# genPWM.net
KiCad netlist of a schematic drawn in Altium Designer
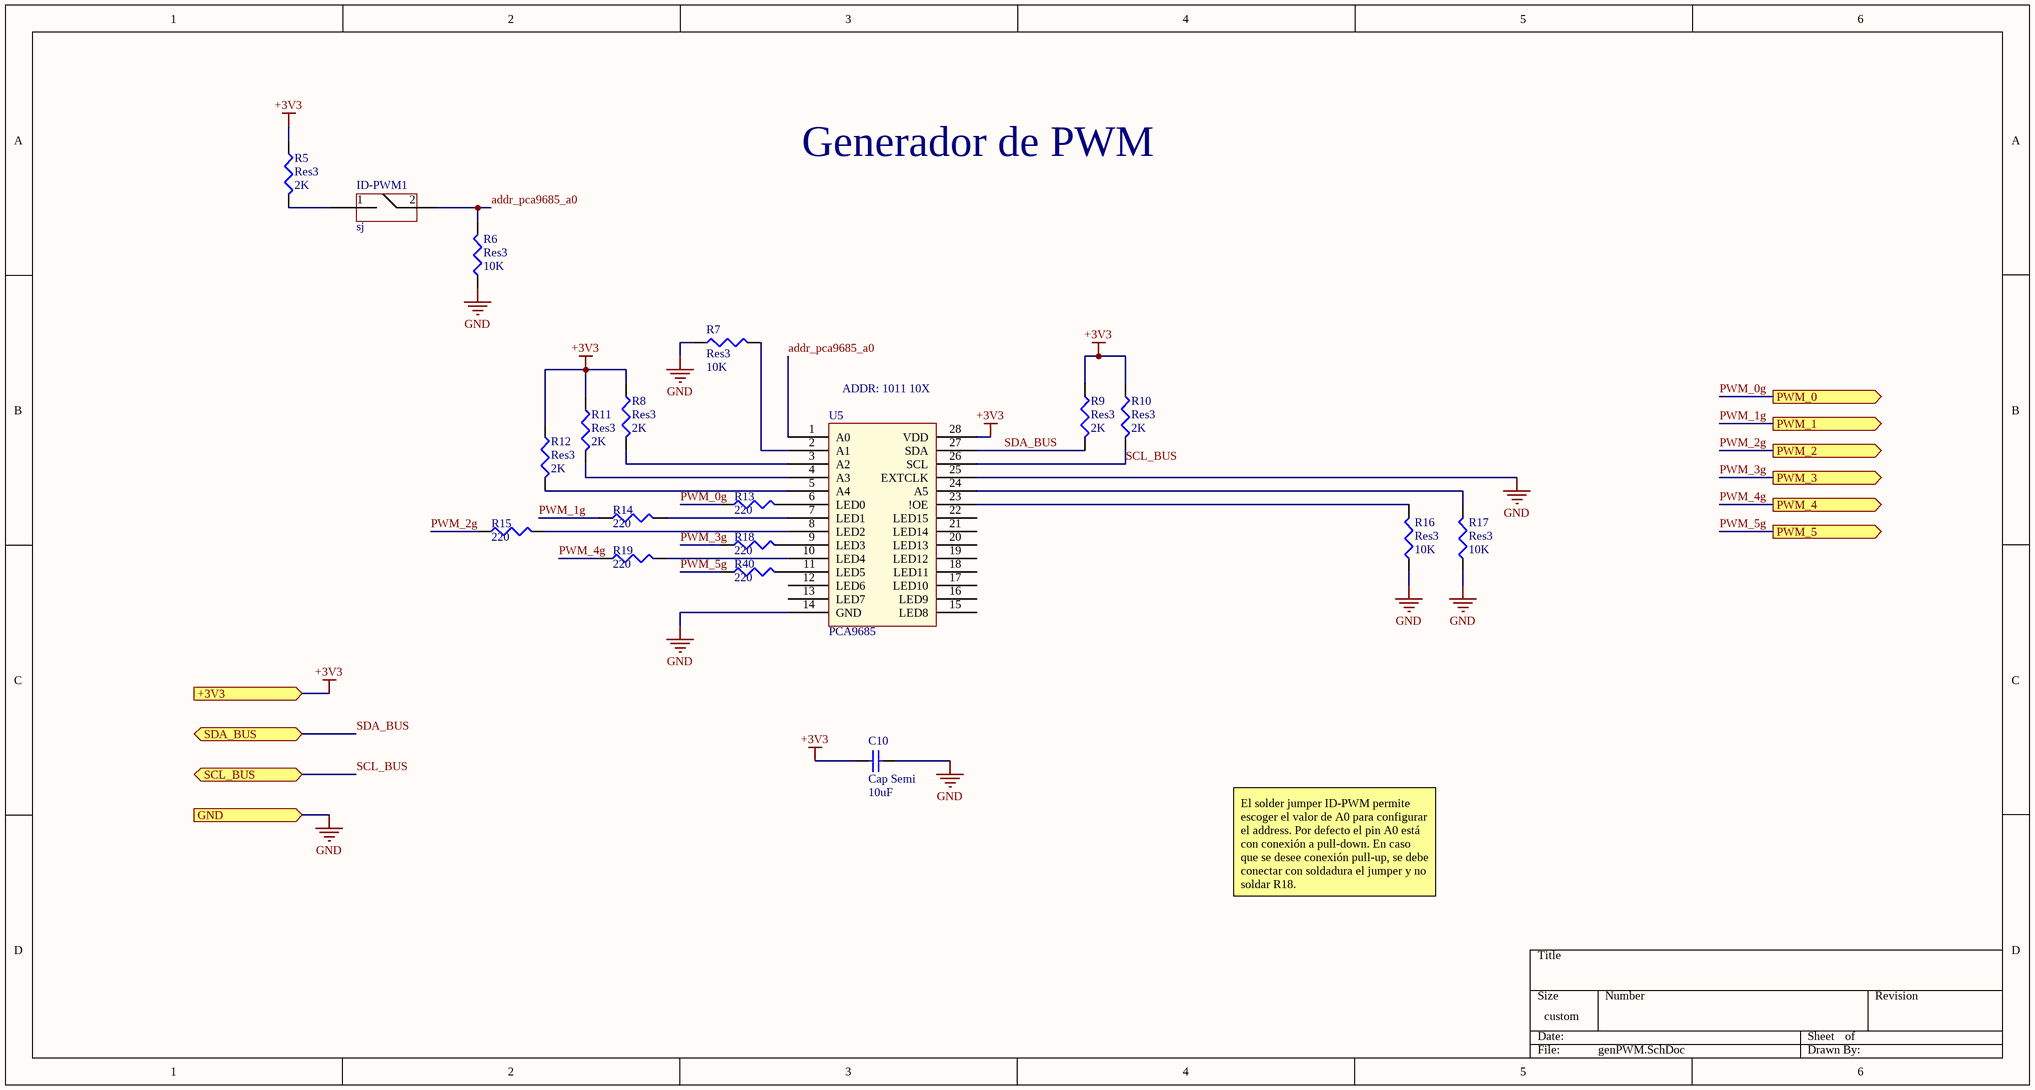
[diagram p0: genPWM.SchDoc]

(export (version "E")
  (design (tool "Eeschema 10.0.6"))
  (components
    (comp (ref "C10")
      (value "Cap Semi")
      (footprint "1608[0603]")
      (description "Capacitor (Semiconductor SIM Model)")
      (fields
        (field (name "ALTIUM_VALUE") "10uF")
        (field (name "MANUFACTURER") "Samsung Electro-Mechanics")
        (field (name "MANUFACTURER PART NUMBER") "CL10A106MQ8NNNC")
        (field (name "PUBLISHER") "Altium Limited")
      )
      (libsource (lib "Miscellaneous Devices") (part "Cap Semi"))
    )
    (comp (ref "ID-PWM1")
      (value "sj")
      (footprint "SJ2")
      (description "solder jumper generic")
      (libsource (lib "IoWLabs") (part "Jumper"))
    )
    (comp (ref "R5")
      (value "Res3")
      (footprint "J1-0603")
      (description "Resistor")
      (fields
        (field (name "ALTIUM_VALUE") "2K")
        (field (name "MANUFACTURER") "YAGEO")
        (field (name "MANUFACTURER PART NUMBER") "RC0603FR-072KL")
        (field (name "PUBLISHER") "Altium Limited")
      )
      (libsource (lib "Miscellaneous Devices") (part "Res3"))
    )
    (comp (ref "R6")
      (value "Res3")
      (footprint "J1-0603")
      (description "Resistor")
      (fields
        (field (name "ALTIUM_VALUE") "10K")
        (field (name "MANUFACTURER") "PANASONIC")
        (field (name "MANUFACTURER PART NUMBER") "ERJPA3F1002V")
        (field (name "PUBLISHER") "Altium Limited")
      )
      (libsource (lib "Miscellaneous Devices") (part "Res3"))
    )
    (comp (ref "R7")
      (value "Res3")
      (footprint "J1-0603")
      (description "Resistor")
      (fields
        (field (name "ALTIUM_VALUE") "10K")
        (field (name "MANUFACTURER") "PANASONIC")
        (field (name "MANUFACTURER PART NUMBER") "ERJPA3F1002V")
        (field (name "PUBLISHER") "Altium Limited")
      )
      (libsource (lib "Miscellaneous Devices") (part "Res3"))
    )
    (comp (ref "R8")
      (value "Res3")
      (footprint "J1-0603")
      (description "Resistor")
      (fields
        (field (name "ALTIUM_VALUE") "2K")
        (field (name "MANUFACTURER") "YAGEO")
        (field (name "MANUFACTURER PART NUMBER") "RC0603FR-072KL")
        (field (name "PUBLISHER") "Altium Limited")
      )
      (libsource (lib "Miscellaneous Devices") (part "Res3"))
    )
    (comp (ref "R9")
      (value "Res3")
      (footprint "J1-0603")
      (description "Resistor")
      (fields
        (field (name "ALTIUM_VALUE") "2K")
        (field (name "MANUFACTURER") "YAGEO")
        (field (name "MANUFACTURER PART NUMBER") "RC0603FR-072KL")
        (field (name "PUBLISHER") "Altium Limited")
      )
      (libsource (lib "Miscellaneous Devices") (part "Res3"))
    )
    (comp (ref "R10")
      (value "Res3")
      (footprint "J1-0603")
      (description "Resistor")
      (fields
        (field (name "ALTIUM_VALUE") "2K")
        (field (name "MANUFACTURER") "YAGEO")
        (field (name "MANUFACTURER PART NUMBER") "RC0603FR-072KL")
        (field (name "PUBLISHER") "Altium Limited")
      )
      (libsource (lib "Miscellaneous Devices") (part "Res3"))
    )
    (comp (ref "R11")
      (value "Res3")
      (footprint "J1-0603")
      (description "Resistor")
      (fields
        (field (name "ALTIUM_VALUE") "2K")
        (field (name "MANUFACTURER") "YAGEO")
        (field (name "MANUFACTURER PART NUMBER") "RC0603FR-072KL")
        (field (name "PUBLISHER") "Altium Limited")
      )
      (libsource (lib "Miscellaneous Devices") (part "Res3"))
    )
    (comp (ref "R12")
      (value "Res3")
      (footprint "J1-0603")
      (description "Resistor")
      (fields
        (field (name "ALTIUM_VALUE") "2K")
        (field (name "MANUFACTURER") "YAGEO")
        (field (name "MANUFACTURER PART NUMBER") "RC0603FR-072KL")
        (field (name "PUBLISHER") "Altium Limited")
      )
      (libsource (lib "Miscellaneous Devices") (part "Res3"))
    )
    (comp (ref "R13")
      (value "220")
      (footprint "J1-0603")
      (description "Resistor")
      (fields
        (field (name "MANUFACTURER PART NUMBER") "RC0603FR-07220RL")
        (field (name "MANUFACTURER") "YAGEO")
        (field (name "PUBLISHER") "Altium Limited")
      )
      (libsource (lib "Miscellaneous Devices") (part "Res3"))
    )
    (comp (ref "R14")
      (value "220")
      (footprint "J1-0603")
      (description "Resistor")
      (fields
        (field (name "MANUFACTURER PART NUMBER") "RC0603FR-07220RL")
        (field (name "MANUFACTURER") "YAGEO")
        (field (name "PUBLISHER") "Altium Limited")
      )
      (libsource (lib "Miscellaneous Devices") (part "Res3"))
    )
    (comp (ref "R15")
      (value "220")
      (footprint "J1-0603")
      (description "Resistor")
      (fields
        (field (name "MANUFACTURER PART NUMBER") "RC0603FR-07220RL")
        (field (name "MANUFACTURER") "YAGEO")
        (field (name "PUBLISHER") "Altium Limited")
      )
      (libsource (lib "Miscellaneous Devices") (part "Res3"))
    )
    (comp (ref "R16")
      (value "Res3")
      (footprint "J1-0603")
      (description "Resistor")
      (fields
        (field (name "ALTIUM_VALUE") "10K")
        (field (name "MANUFACTURER") "PANASONIC")
        (field (name "MANUFACTURER PART NUMBER") "ERJPA3F1002V")
        (field (name "PUBLISHER") "Altium Limited")
      )
      (libsource (lib "Miscellaneous Devices") (part "Res3"))
    )
    (comp (ref "R17")
      (value "Res3")
      (footprint "J1-0603")
      (description "Resistor")
      (fields
        (field (name "ALTIUM_VALUE") "10K")
        (field (name "MANUFACTURER") "PANASONIC")
        (field (name "MANUFACTURER PART NUMBER") "ERJPA3F1002V")
        (field (name "PUBLISHER") "Altium Limited")
      )
      (libsource (lib "Miscellaneous Devices") (part "Res3"))
    )
    (comp (ref "R18")
      (value "220")
      (footprint "J1-0603")
      (description "Resistor")
      (fields
        (field (name "MANUFACTURER PART NUMBER") "RC0603FR-07220RL")
        (field (name "MANUFACTURER") "YAGEO")
        (field (name "PUBLISHER") "Altium Limited")
      )
      (libsource (lib "Miscellaneous Devices") (part "Res3"))
    )
    (comp (ref "R19")
      (value "220")
      (footprint "J1-0603")
      (description "Resistor")
      (fields
        (field (name "MANUFACTURER PART NUMBER") "RC0603FR-07220RL")
        (field (name "MANUFACTURER") "YAGEO")
        (field (name "PUBLISHER") "Altium Limited")
      )
      (libsource (lib "Miscellaneous Devices") (part "Res3"))
    )
    (comp (ref "R40")
      (value "220")
      (footprint "J1-0603")
      (description "Resistor")
      (fields
        (field (name "MANUFACTURER PART NUMBER") "RC0603FR-07220RL")
        (field (name "MANUFACTURER") "YAGEO")
        (field (name "PUBLISHER") "Altium Limited")
      )
      (libsource (lib "Miscellaneous Devices") (part "Res3"))
    )
    (comp (ref "U5")
      (value "PCA9685")
      (footprint "SSOP-28_L")
      (description "LED Drivers,16CH, I2C, TSSOP-28")
      (fields
        (field (name "MANUFACTURER") "NXP Semicon")
        (field (name "MANUFACTURER PART NUMBER") "PCA9685PW/Q900,118")
      )
      (libsource (lib "IoWLabs") (part "PCA9685"))
    )
  )
  (nets
    (net (code "1") (name "+3V3") (class "Default")
      (node (ref "C10") (pin "2") (pinfunction "2_2") (pintype "passive"))
      (node (ref "R10") (pin "1") (pinfunction "1_1") (pintype "passive"))
      (node (ref "R11") (pin "1") (pinfunction "1_1") (pintype "passive"))
      (node (ref "R12") (pin "1") (pinfunction "1_1") (pintype "passive"))
      (node (ref "R5") (pin "1") (pinfunction "1_1") (pintype "passive"))
      (node (ref "R8") (pin "1") (pinfunction "1_1") (pintype "passive"))
      (node (ref "R9") (pin "1") (pinfunction "1_1") (pintype "passive"))
      (node (ref "U5") (pin "28") (pinfunction "VDD_28") (pintype "passive"))
    )
    (net (code "2") (name "/PWM_0g") (class "Default")
      (node (ref "R13") (pin "1") (pinfunction "1_1") (pintype "passive"))
    )
    (net (code "3") (name "/PWM_1g") (class "Default")
      (node (ref "R14") (pin "1") (pinfunction "1_1") (pintype "passive"))
    )
    (net (code "4") (name "/PWM_2g") (class "Default")
      (node (ref "R15") (pin "1") (pinfunction "1_1") (pintype "passive"))
    )
    (net (code "5") (name "/PWM_3g") (class "Default")
      (node (ref "R18") (pin "1") (pinfunction "1_1") (pintype "passive"))
    )
    (net (code "6") (name "/PWM_4g") (class "Default")
      (node (ref "R19") (pin "1") (pinfunction "1_1") (pintype "passive"))
    )
    (net (code "7") (name "/PWM_5g") (class "Default")
      (node (ref "R40") (pin "1") (pinfunction "1_1") (pintype "passive"))
    )
    (net (code "8") (name "/SCL_BUS") (class "Default")
      (node (ref "R10") (pin "2") (pinfunction "2_2") (pintype "passive"))
      (node (ref "U5") (pin "26") (pinfunction "SCL_26") (pintype "passive"))
    )
    (net (code "9") (name "/SDA_BUS") (class "Default")
      (node (ref "R9") (pin "2") (pinfunction "2_2") (pintype "passive"))
      (node (ref "U5") (pin "27") (pinfunction "SDA_27") (pintype "passive"))
    )
    (net (code "10") (name "/addr_pca9685_a0") (class "Default")
      (node (ref "ID-PWM1") (pin "2") (pinfunction "2_2") (pintype "passive"))
      (node (ref "R6") (pin "2") (pinfunction "2_2") (pintype "passive"))
      (node (ref "U5") (pin "1") (pinfunction "A0_1") (pintype "passive"))
    )
    (net (code "11") (name "GND") (class "Default")
      (node (ref "C10") (pin "1") (pinfunction "1_1") (pintype "passive"))
      (node (ref "R16") (pin "1") (pinfunction "1_1") (pintype "passive"))
      (node (ref "R17") (pin "1") (pinfunction "1_1") (pintype "passive"))
      (node (ref "R6") (pin "1") (pinfunction "1_1") (pintype "passive"))
      (node (ref "R7") (pin "1") (pinfunction "1_1") (pintype "passive"))
      (node (ref "U5") (pin "14") (pinfunction "GND_14") (pintype "passive"))
      (node (ref "U5") (pin "25") (pinfunction "EXTCLK_25") (pintype "passive"))
    )
    (net (code "12") (name "Net-(ID-PWM1-Pad1)") (class "Default")
      (node (ref "ID-PWM1") (pin "1") (pinfunction "1_1") (pintype "passive"))
      (node (ref "R5") (pin "2") (pinfunction "2_2") (pintype "passive"))
    )
    (net (code "13") (name "Net-(U5-!OE)") (class "Default")
      (node (ref "R16") (pin "2") (pinfunction "2_2") (pintype "passive"))
      (node (ref "U5") (pin "23") (pinfunction "!OE_23") (pintype "passive"))
    )
    (net (code "14") (name "Net-(U5-A1)") (class "Default")
      (node (ref "R7") (pin "2") (pinfunction "2_2") (pintype "passive"))
      (node (ref "U5") (pin "2") (pinfunction "A1_2") (pintype "passive"))
    )
    (net (code "15") (name "Net-(U5-A2)") (class "Default")
      (node (ref "R8") (pin "2") (pinfunction "2_2") (pintype "passive"))
      (node (ref "U5") (pin "3") (pinfunction "A2_3") (pintype "passive"))
    )
    (net (code "16") (name "Net-(U5-A3)") (class "Default")
      (node (ref "R11") (pin "2") (pinfunction "2_2") (pintype "passive"))
      (node (ref "U5") (pin "4") (pinfunction "A3_4") (pintype "passive"))
    )
    (net (code "17") (name "Net-(U5-A4)") (class "Default")
      (node (ref "R12") (pin "2") (pinfunction "2_2") (pintype "passive"))
      (node (ref "U5") (pin "5") (pinfunction "A4_5") (pintype "passive"))
    )
    (net (code "18") (name "Net-(U5-A5)") (class "Default")
      (node (ref "R17") (pin "2") (pinfunction "2_2") (pintype "passive"))
      (node (ref "U5") (pin "24") (pinfunction "A5_24") (pintype "passive"))
    )
    (net (code "19") (name "Net-(U5-LED0)") (class "Default")
      (node (ref "R13") (pin "2") (pinfunction "2_2") (pintype "passive"))
      (node (ref "U5") (pin "6") (pinfunction "LED0_6") (pintype "passive"))
    )
    (net (code "20") (name "Net-(U5-LED1)") (class "Default")
      (node (ref "R14") (pin "2") (pinfunction "2_2") (pintype "passive"))
      (node (ref "U5") (pin "7") (pinfunction "LED1_7") (pintype "passive"))
    )
    (net (code "21") (name "Net-(U5-LED2)") (class "Default")
      (node (ref "R15") (pin "2") (pinfunction "2_2") (pintype "passive"))
      (node (ref "U5") (pin "8") (pinfunction "LED2_8") (pintype "passive"))
    )
    (net (code "22") (name "Net-(U5-LED3)") (class "Default")
      (node (ref "R18") (pin "2") (pinfunction "2_2") (pintype "passive"))
      (node (ref "U5") (pin "9") (pinfunction "LED3_9") (pintype "passive"))
    )
    (net (code "23") (name "Net-(U5-LED4)") (class "Default")
      (node (ref "R19") (pin "2") (pinfunction "2_2") (pintype "passive"))
      (node (ref "U5") (pin "10") (pinfunction "LED4_10") (pintype "passive"))
    )
    (net (code "24") (name "Net-(U5-LED5)") (class "Default")
      (node (ref "R40") (pin "2") (pinfunction "2_2") (pintype "passive"))
      (node (ref "U5") (pin "11") (pinfunction "LED5_11") (pintype "passive"))
    )
    (net (code "25") (name "unconnected-(U5-LED6-Pad12)") (class "Default")
      (node (ref "U5") (pin "12") (pinfunction "LED6_12") (pintype "passive"))
    )
    (net (code "26") (name "unconnected-(U5-LED7-Pad13)") (class "Default")
      (node (ref "U5") (pin "13") (pinfunction "LED7_13") (pintype "passive"))
    )
    (net (code "27") (name "unconnected-(U5-LED8-Pad15)") (class "Default")
      (node (ref "U5") (pin "15") (pinfunction "LED8_15") (pintype "passive"))
    )
    (net (code "28") (name "unconnected-(U5-LED9-Pad16)") (class "Default")
      (node (ref "U5") (pin "16") (pinfunction "LED9_16") (pintype "passive"))
    )
    (net (code "29") (name "unconnected-(U5-LED10-Pad17)") (class "Default")
      (node (ref "U5") (pin "17") (pinfunction "LED10_17") (pintype "passive"))
    )
    (net (code "30") (name "unconnected-(U5-LED11-Pad18)") (class "Default")
      (node (ref "U5") (pin "18") (pinfunction "LED11_18") (pintype "passive"))
    )
    (net (code "31") (name "unconnected-(U5-LED12-Pad19)") (class "Default")
      (node (ref "U5") (pin "19") (pinfunction "LED12_19") (pintype "passive"))
    )
    (net (code "32") (name "unconnected-(U5-LED13-Pad20)") (class "Default")
      (node (ref "U5") (pin "20") (pinfunction "LED13_20") (pintype "passive"))
    )
    (net (code "33") (name "unconnected-(U5-LED14-Pad21)") (class "Default")
      (node (ref "U5") (pin "21") (pinfunction "LED14_21") (pintype "passive"))
    )
    (net (code "34") (name "unconnected-(U5-LED15-Pad22)") (class "Default")
      (node (ref "U5") (pin "22") (pinfunction "LED15_22") (pintype "passive"))
    )
  )
)
